# Varaible_power_supply.net
KiCad netlist of a schematic drawn in EAGLE
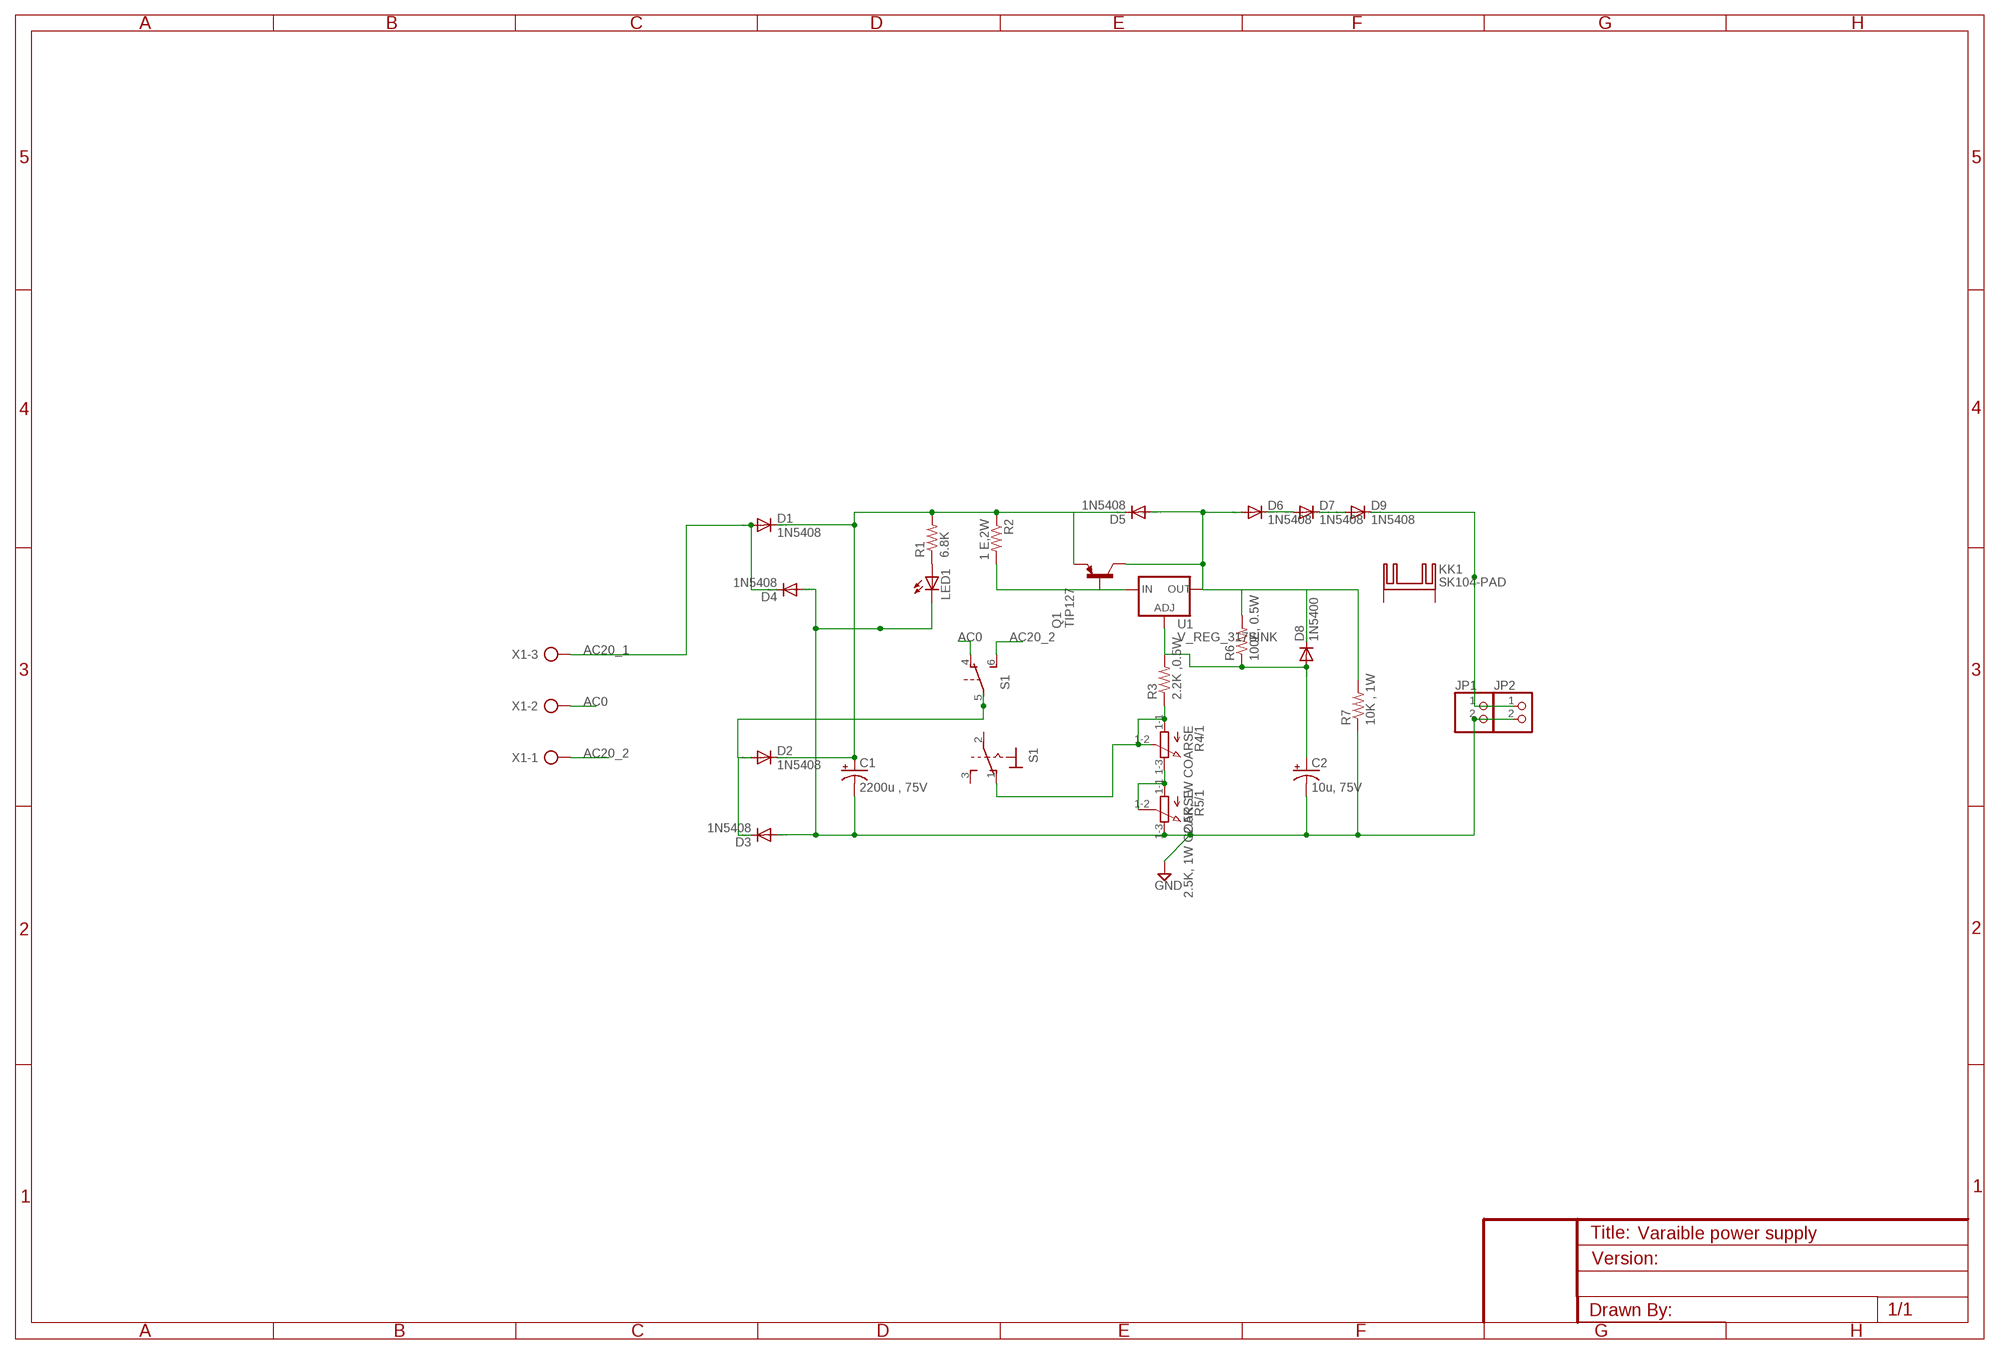
[diagram p0: schematic, sheet 1]

(export (version "E")
  (design (tool "Eeschema 10.0.6"))
  (components
    (comp (ref "C1")
      (value "2200u , 75V")
      (footprint "eagle-import:E5-13")
      (libsource (lib "eagle-import") (part "CPOL-USE5-13"))
    )
    (comp (ref "C2")
      (value "10u, 75V")
      (footprint "eagle-import:E5-13")
      (libsource (lib "eagle-import") (part "CPOL-USE5-13"))
    )
    (comp (ref "D1")
      (value "1N5408")
      (footprint "eagle-import:DO201-15")
      (libsource (lib "eagle-import") (part "1N5400"))
    )
    (comp (ref "D2")
      (value "1N5408")
      (footprint "eagle-import:DO201-15")
      (libsource (lib "eagle-import") (part "1N5400"))
    )
    (comp (ref "D3")
      (value "1N5408")
      (footprint "eagle-import:DO201-15")
      (libsource (lib "eagle-import") (part "1N5400"))
    )
    (comp (ref "D4")
      (value "1N5408")
      (footprint "eagle-import:DO201-15")
      (libsource (lib "eagle-import") (part "1N5400"))
    )
    (comp (ref "D5")
      (value "1N5408")
      (footprint "eagle-import:DO201-15")
      (libsource (lib "eagle-import") (part "diode_210_1N5400"))
    )
    (comp (ref "D6")
      (value "1N5408")
      (footprint "eagle-import:DO201-15")
      (libsource (lib "eagle-import") (part "diode_210_1N5400"))
    )
    (comp (ref "D7")
      (value "1N5408")
      (footprint "eagle-import:DO201-15")
      (libsource (lib "eagle-import") (part "diode_210_1N5400"))
    )
    (comp (ref "D8")
      (value "1N5400")
      (footprint "eagle-import:DO201-15")
      (libsource (lib "eagle-import") (part "diode_210_1N5400"))
    )
    (comp (ref "D9")
      (value "1N5408")
      (footprint "eagle-import:DO201-15")
      (libsource (lib "eagle-import") (part "diode_210_1N5400"))
    )
    (comp (ref "JP1")
      (value "PINHD-1X2")
      (footprint "eagle-import:1X02")
      (libsource (lib "eagle-import") (part "PINHD-1X2"))
    )
    (comp (ref "JP2")
      (value "PINHD-1X2")
      (footprint "eagle-import:1X02")
      (libsource (lib "eagle-import") (part "PINHD-1X2"))
    )
    (comp (ref "KK1")
      (value "SK104-PAD")
      (footprint "eagle-import:SK104-PAD")
      (libsource (lib "eagle-import") (part "SK104-PAD"))
    )
    (comp (ref "LED1")
      (value "LED5MM")
      (footprint "eagle-import:LED5MM")
      (libsource (lib "eagle-import") (part "LED5MM"))
    )
    (comp (ref "Q1")
      (value "TIP127")
      (footprint "eagle-import:TO220")
      (libsource (lib "eagle-import") (part "TIP30"))
    )
    (comp (ref "R1")
      (value "6.8K")
      (footprint "eagle-import:0411_15")
      (libsource (lib "eagle-import") (part "R-US_0411/15"))
    )
    (comp (ref "R2")
      (value "1 E,2W")
      (footprint "eagle-import:0411_15")
      (libsource (lib "eagle-import") (part "R-US_0411/15"))
    )
    (comp (ref "R3")
      (value "2.2K ,0.5W")
      (footprint "eagle-import:0411_15")
      (libsource (lib "eagle-import") (part "R-US_0411/15"))
    )
    (comp (ref "R4")
      (value "2.5K, 1W COARSE")
      (footprint "eagle-import:3RP_1610G")
      (libsource (lib "eagle-import") (part "3RP/1610G"))
    )
    (comp (ref "R5")
      (value "2.5K, 1W COARSE")
      (footprint "eagle-import:3RP_1610G")
      (libsource (lib "eagle-import") (part "3RP/1610G"))
    )
    (comp (ref "R6")
      (value "100E, 0.5W")
      (footprint "eagle-import:0411_15")
      (libsource (lib "eagle-import") (part "R-US_0411/15"))
    )
    (comp (ref "R7")
      (value "10K , 1W")
      (footprint "eagle-import:0411_15")
      (libsource (lib "eagle-import") (part "R-US_0411/15"))
    )
    (comp (ref "S1")
      (value "320-938")
      (footprint "eagle-import:320-938")
      (libsource (lib "eagle-import") (part "320-938"))
    )
    (comp (ref "U1")
      (value "V_REG_317SINK")
      (footprint "eagle-import:TO220-ADJ")
      (libsource (lib "eagle-import") (part "V_REG_317SINK"))
    )
    (comp (ref "X1")
      (value "AK500/3-H")
      (footprint "eagle-import:AK500_3-H")
      (libsource (lib "eagle-import") (part "AK500/3-H"))
    )
  )
  (nets
    (net (code "1") (name "/AC0") (class "Default")
      (node (ref "S1") (pin "4") (pinfunction "O_4") (pintype "passive"))
      (node (ref "X1") (pin "2") (pinfunction "KL_2") (pintype "passive"))
    )
    (net (code "2") (name "/AC20_1") (class "Default")
      (node (ref "D1") (pin "A") (pinfunction "A_A") (pintype "passive"))
      (node (ref "D4") (pin "C") (pinfunction "C_C") (pintype "passive"))
      (node (ref "X1") (pin "3") (pinfunction "KL_3") (pintype "passive"))
    )
    (net (code "3") (name "/AC20_2") (class "Default")
      (node (ref "S1") (pin "6") (pinfunction "S_6") (pintype "passive"))
      (node (ref "X1") (pin "1") (pinfunction "KL_1") (pintype "passive"))
    )
    (net (code "4") (name "GND") (class "Default")
      (node (ref "C1") (pin "-") (pinfunction "-_-") (pintype "passive"))
      (node (ref "C2") (pin "-") (pinfunction "-_-") (pintype "passive"))
      (node (ref "D3") (pin "A") (pinfunction "A_A") (pintype "passive"))
      (node (ref "D4") (pin "A") (pinfunction "A_A") (pintype "passive"))
      (node (ref "JP1") (pin "2") (pinfunction "2_2") (pintype "passive"))
      (node (ref "JP2") (pin "2") (pinfunction "2_2") (pintype "passive"))
      (node (ref "LED1") (pin "K") (pinfunction "C_K") (pintype "passive"))
      (node (ref "R5") (pin "1-3") (pinfunction "E_1-3") (pintype "passive"))
      (node (ref "R7") (pin "1") (pinfunction "1_1") (pintype "passive"))
    )
    (net (code "5") (name "Net-(C2-Pad+)") (class "Default")
      (node (ref "C2") (pin "+") (pinfunction "+_+") (pintype "passive"))
      (node (ref "D8") (pin "A") (pinfunction "A_A") (pintype "passive"))
      (node (ref "R3") (pin "2") (pinfunction "2_2") (pintype "passive"))
      (node (ref "R6") (pin "1") (pinfunction "1_1") (pintype "passive"))
      (node (ref "U1") (pin "ADJ") (pinfunction "ADJ_ADJ") (pintype "input"))
    )
    (net (code "6") (name "Net-(D6-PadC)") (class "Default")
      (node (ref "D6") (pin "C") (pinfunction "C_C") (pintype "passive"))
      (node (ref "D7") (pin "A") (pinfunction "A_A") (pintype "passive"))
    )
    (net (code "7") (name "Net-(D7-PadC)") (class "Default")
      (node (ref "D7") (pin "C") (pinfunction "C_C") (pintype "passive"))
      (node (ref "D9") (pin "A") (pinfunction "A_A") (pintype "passive"))
    )
    (net (code "8") (name "Net-(D9-PadC)") (class "Default")
      (node (ref "D9") (pin "C") (pinfunction "C_C") (pintype "passive"))
      (node (ref "JP1") (pin "1") (pinfunction "1_1") (pintype "passive"))
      (node (ref "JP2") (pin "1") (pinfunction "1_1") (pintype "passive"))
    )
    (net (code "9") (name "Net-(LED1-PadA)") (class "Default")
      (node (ref "LED1") (pin "A") (pinfunction "A_A") (pintype "passive"))
      (node (ref "R1") (pin "1") (pinfunction "1_1") (pintype "passive"))
    )
    (net (code "10") (name "Net-(Q1-B)") (class "Default")
      (node (ref "Q1") (pin "1") (pinfunction "B_1") (pintype "passive"))
      (node (ref "R2") (pin "2") (pinfunction "2_2") (pintype "passive"))
      (node (ref "U1") (pin "IN") (pinfunction "IN_IN") (pintype "input"))
    )
    (net (code "11") (name "Net-(Q1-C)") (class "Default")
      (node (ref "D5") (pin "A") (pinfunction "A_A") (pintype "passive"))
      (node (ref "D6") (pin "A") (pinfunction "A_A") (pintype "passive"))
      (node (ref "D8") (pin "C") (pinfunction "C_C") (pintype "passive"))
      (node (ref "Q1") (pin "2") (pinfunction "C_2") (pintype "passive"))
      (node (ref "R6") (pin "2") (pinfunction "2_2") (pintype "passive"))
      (node (ref "R7") (pin "2") (pinfunction "2_2") (pintype "passive"))
      (node (ref "U1") (pin "OUT") (pinfunction "OUT_OUT") (pintype "output"))
    )
    (net (code "12") (name "Net-(Q1-E)") (class "Default")
      (node (ref "C1") (pin "+") (pinfunction "+_+") (pintype "passive"))
      (node (ref "D1") (pin "C") (pinfunction "C_C") (pintype "passive"))
      (node (ref "D2") (pin "C") (pinfunction "C_C") (pintype "passive"))
      (node (ref "D5") (pin "C") (pinfunction "C_C") (pintype "passive"))
      (node (ref "Q1") (pin "3") (pinfunction "E_3") (pintype "passive"))
      (node (ref "R1") (pin "2") (pinfunction "2_2") (pintype "passive"))
      (node (ref "R2") (pin "1") (pinfunction "1_1") (pintype "passive"))
    )
    (net (code "13") (name "Net-(R4A-A)") (class "Default")
      (node (ref "R3") (pin "1") (pinfunction "1_1") (pintype "passive"))
      (node (ref "R4") (pin "1-1") (pinfunction "A_1-1") (pintype "passive"))
      (node (ref "R4") (pin "1-2") (pinfunction "S_1-2") (pintype "passive"))
      (node (ref "S1") (pin "1") (pinfunction "O_1") (pintype "passive"))
    )
    (net (code "14") (name "Net-(R4A-E)") (class "Default")
      (node (ref "R4") (pin "1-3") (pinfunction "E_1-3") (pintype "passive"))
      (node (ref "R5") (pin "1-1") (pinfunction "A_1-1") (pintype "passive"))
      (node (ref "R5") (pin "1-2") (pinfunction "S_1-2") (pintype "passive"))
    )
    (net (code "15") (name "Net-(S1B-P)") (class "Default")
      (node (ref "D2") (pin "A") (pinfunction "A_A") (pintype "passive"))
      (node (ref "D3") (pin "C") (pinfunction "C_C") (pintype "passive"))
      (node (ref "S1") (pin "5") (pinfunction "P_5") (pintype "passive"))
    )
    (net (code "16") (name "unconnected-(KK1-K-PadK1)") (class "Default")
      (node (ref "KK1") (pin "K1") (pinfunction "K_K1") (pintype "passive"))
    )
    (net (code "17") (name "unconnected-(KK1-K-PadK2)") (class "Default")
      (node (ref "KK1") (pin "K2") (pinfunction "K_K2") (pintype "passive"))
    )
    (net (code "18") (name "unconnected-(S1A-P-Pad2)") (class "Default")
      (node (ref "S1") (pin "2") (pinfunction "P_2") (pintype "passive"))
    )
    (net (code "19") (name "unconnected-(S1A-S-Pad3)") (class "Default")
      (node (ref "S1") (pin "3") (pinfunction "S_3") (pintype "passive"))
    )
  )
)
